# ESP32_LHCbit.net
KiCad netlist of a schematic drawn in Altium Designer
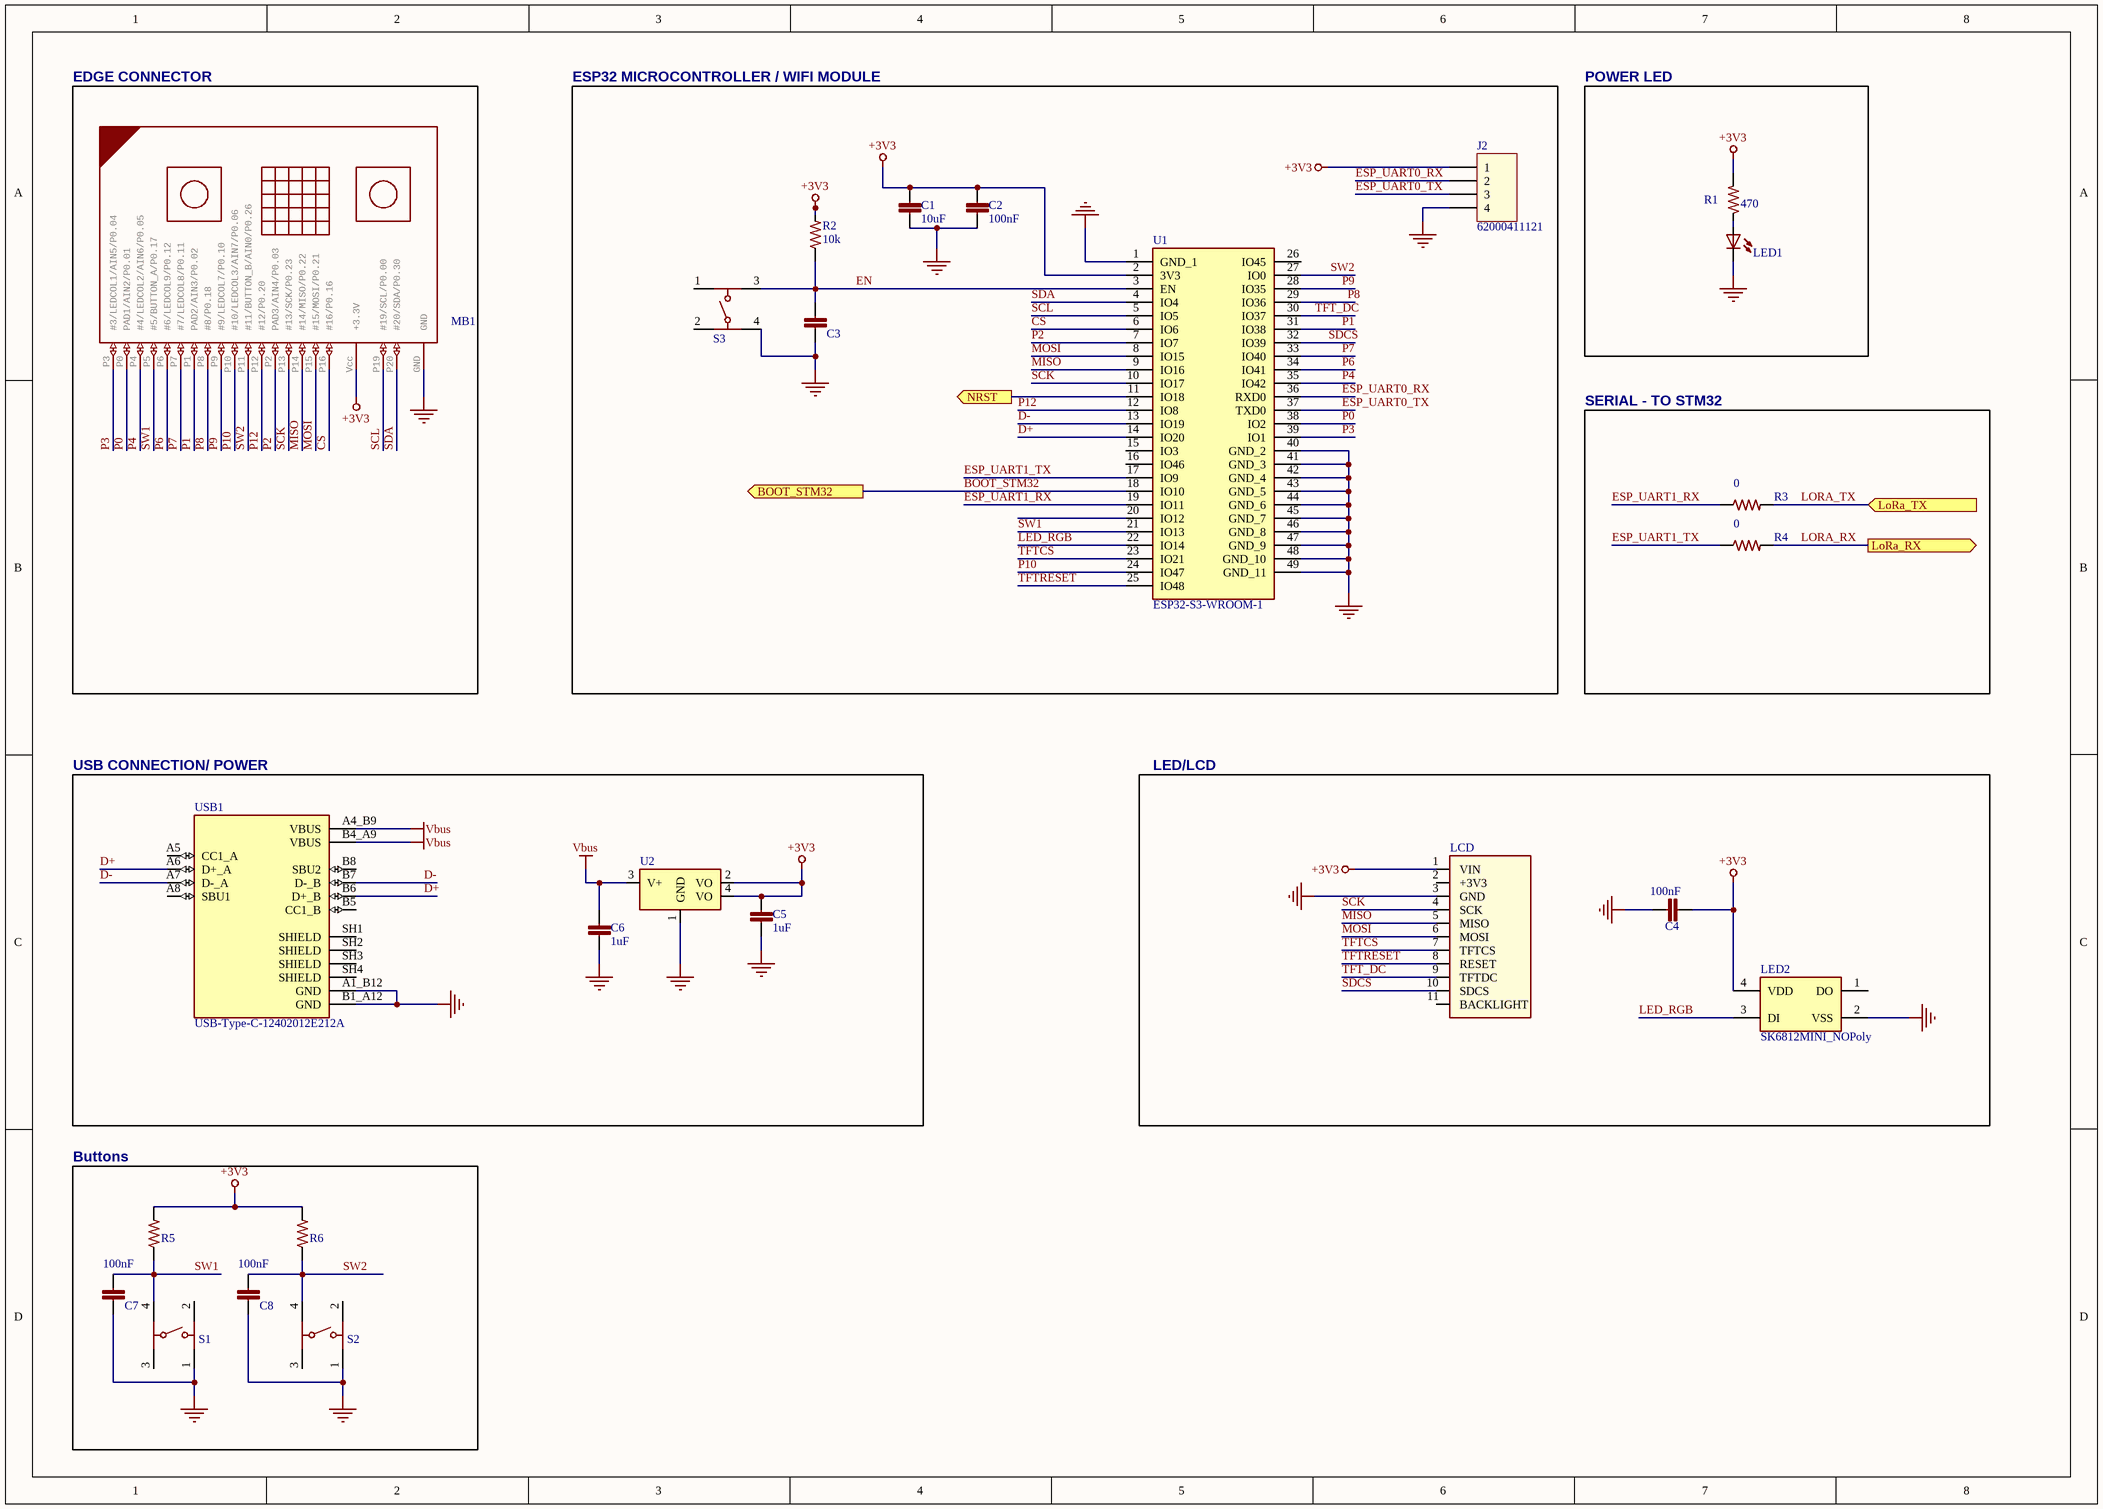
[diagram p0: ESP32_LHCbit.SchDoc]

(export (version "E")
  (design (tool "Eeschema 10.0.6"))
  (components
    (comp (ref "C1")
      (value "10uF")
      (footprint "C0603")
      (fields (field (name "PART NUMBER") "CL10A106KP8NNNC") (field (name "Comment") "C-EUC0603"))
      (libsource (lib "rcl") (part "C-EUC0603"))
    )
    (comp (ref "C2")
      (value "100nF")
      (footprint "C0603")
      (fields (field (name "PART NUMBER") "CC0603KRX7R9BB104") (field (name "Comment") "C-EUC0603"))
      (libsource (lib "rcl") (part "C-EUC0603"))
    )
    (comp (ref "C3")
      (value "C-EUC0402")
      (footprint "C0402")
      (fields (field (name "PART NUMBER") "C0402C104K8"))
      (libsource (lib "") (part "C-EUC0402_1"))
    )
    (comp (ref "C4")
      (value "100nF")
      (footprint "C0402")
      (fields (field (name "PART NUMBER") "C0402C104K8") (field (name "Comment") "C-EUC0402"))
      (libsource (lib "rcl") (part "C-EUC0402"))
    )
    (comp (ref "C5")
      (value "1uF")
      (footprint "C0603")
      (fields (field (name "PART NUMBER") "CL10A105KO8NNNC") (field (name "Comment") "C-EUC0603"))
      (libsource (lib "") (part "C-EUC0603_1"))
    )
    (comp (ref "C6")
      (value "1uF")
      (footprint "C0603")
      (fields (field (name "PART NUMBER") "CL10A105KO8NNNC") (field (name "Comment") "C-EUC0603"))
      (libsource (lib "") (part "C-EUC0603_1"))
    )
    (comp (ref "C7")
      (value "100nF")
      (footprint "C0402")
      (fields (field (name "PART NUMBER") "C0402C104K8") (field (name "Comment") "C-EUC0402"))
      (libsource (lib "") (part "C-EUC0402_1"))
    )
    (comp (ref "C8")
      (value "100nF")
      (footprint "C0402")
      (fields (field (name "PART NUMBER") "C0402C104K8") (field (name "Comment") "C-EUC0402"))
      (libsource (lib "") (part "C-EUC0402_1"))
    )
    (comp (ref "J2")
      (value "62000411121")
      (footprint "62000411121")
      (description "WR-PHD 2.00 mm THT Pin Header, 4p")
      (libsource (lib "Male_header_200mm") (part "62000411121"))
    )
    (comp (ref "LCD")
      (value "Adafruit 0.96\"  TFT LCD")
      (footprint "ADafruit 0.96 Display")
      (libsource (lib "TE") (part "Adafruit 0.96{dblquote}  TFT LCD"))
    )
    (comp (ref "LED1")
      (value "~")
      (footprint "CHIPLED_0805")
      (fields (field (name "PART NUMBER") "AP2012EC"))
      (libsource (lib "led") (part "LEDCHIPLED_0805"))
    )
    (comp (ref "LED2")
      (value "SK6812MINI_NOPoly")
      (footprint "WS2812BMINI_no_poly")
      (description "SMD RGB (WS2812/SK6812MINI) 3535")
      (fields (field (name "PART NUMBER") "SK6812MINI"))
      (libsource (lib "led") (part "SK6812MINI_NOPoly"))
    )
    (comp (ref "MB1")
      (value "MICRO:BIT_EDGE")
      (footprint "MICROBIT_EDGE")
      (libsource (lib "TE") (part "MICRO{colon}BIT_EDGE"))
    )
    (comp (ref "R1")
      (value "470")
      (footprint "R0603")
      (fields (field (name "PART NUMBER") "RC0603FR-07470RL") (field (name "Comment") "R-US_R0603"))
      (libsource (lib "rcl") (part "R-US_R0603"))
    )
    (comp (ref "R2")
      (value "10k")
      (footprint "R0402")
      (fields (field (name "PART NUMBER") "RC0402FR-0710KL") (field (name "Comment") "R-US_R0402"))
      (libsource (lib "rcl") (part "R-US_R0402"))
    )
    (comp (ref "R3")
      (value "0")
      (footprint "R0402")
      (fields (field (name "PART NUMBER") "PA0402-R-070RL") (field (name "Comment") "R-US_R0402"))
      (libsource (lib "rcl") (part "R-US_R0402"))
    )
    (comp (ref "R4")
      (value "0")
      (footprint "R0402")
      (fields (field (name "PART NUMBER") "PA0402-R-070RL") (field (name "Comment") "R-US_R0402"))
      (libsource (lib "rcl") (part "R-US_R0402"))
    )
    (comp (ref "R5")
      (value "R-US_R0402")
      (footprint "R0402")
      (fields (field (name "PART NUMBER") "RC0402FR-0710KL"))
      (libsource (lib "rcl") (part "R-US_R0402"))
    )
    (comp (ref "R6")
      (value "R-US_R0402")
      (footprint "R0402")
      (fields (field (name "PART NUMBER") "RC0402FR-0710KL"))
      (libsource (lib "rcl") (part "R-US_R0402"))
    )
    (comp (ref "S1")
      (value "DTSM-6")
      (footprint "4301x20438x6_6x6x4.3_DTSM-6")
      (description "WS-TASV 6x6mm Tact Switch, SMD version")
      (libsource (lib "Switches") (part "DTSM-6"))
    )
    (comp (ref "S2")
      (value "DTSM-6")
      (footprint "4301x20438x6_6x6x4.3_DTSM-6")
      (description "WS-TASV 6x6mm Tact Switch, SMD version")
      (libsource (lib "Switches") (part "DTSM-6"))
    )
    (comp (ref "S3")
      (value "434153017835")
      (footprint "434153017835_3.2x2.9x1.7")
      (description "WS-TASV 3.5x2.9mm Tact Switch, J-Bend SMD version")
      (libsource (lib "Switches") (part "434153017835"))
    )
    (comp (ref "U1")
      (value "ESP32-S3-WROOM-1")
      (footprint "ESP32S3WROOM1N16R2")
      (description "Integrated Circuit")
      (fields (field (name "PART NUMBER") "ESP32-S3-WROOM-1-N16R2"))
      (libsource (lib "TE") (part "ESP32-S3-WROOM-1"))
    )
    (comp (ref "U2")
      (value "NCP1117LP")
      (footprint "SOT223")
      (fields (field (name "PART NUMBER") "TLV1117LV33DCYR"))
      (libsource (lib "TE") (part "NCP1117LP"))
    )
    (comp (ref "USB1")
      (value "USB-Type-C-12402012E212A")
      (footprint "AMPHENOL_12402012E212A")
      (description "USB2.0, Type C")
      (fields (field (name "PART NUMBER") "TYPEC-304-ACP16"))
      (libsource (lib "TE") (part "USB-Type-C-12402012E212A"))
    )
  )
  (nets
    (net (code "1") (name "+3V3") (class "Default")
      (node (ref "C1") (pin "1") (pinfunction "1_1") (pintype "passive"))
      (node (ref "C2") (pin "1") (pinfunction "1_1") (pintype "passive"))
      (node (ref "C4") (pin "2") (pinfunction "2_2") (pintype "passive"))
      (node (ref "C5") (pin "1") (pinfunction "1_1") (pintype "passive"))
      (node (ref "J2") (pin "1") (pinfunction "1_1") (pintype "passive"))
      (node (ref "LCD") (pin "1") (pinfunction "VIN_1") (pintype "power_in"))
      (node (ref "LED2") (pin "4") (pinfunction "VDD_4") (pintype "passive"))
      (node (ref "MB1") (pin "Vcc") (pinfunction "+3.3V_Vcc") (pintype "power_in"))
      (node (ref "R1") (pin "2") (pinfunction "2_2") (pintype "passive"))
      (node (ref "R2") (pin "2") (pinfunction "2_2") (pintype "passive"))
      (node (ref "R5") (pin "2") (pinfunction "2_2") (pintype "passive"))
      (node (ref "R6") (pin "2") (pinfunction "2_2") (pintype "passive"))
      (node (ref "U1") (pin "2") (pinfunction "3V3_2") (pintype "passive"))
      (node (ref "U2") (pin "2") (pinfunction "VO_2") (pintype "passive"))
      (node (ref "U2") (pin "4") (pinfunction "VO_4") (pintype "passive"))
    )
    (net (code "2") (name "/BOOT_STM32") (class "Default")
      (node (ref "U1") (pin "18") (pinfunction "IO10_18") (pintype "passive"))
    )
    (net (code "3") (name "/CS") (class "Default")
      (node (ref "MB1") (pin "P16") (pinfunction "#16/P0.16_P16") (pintype "bidirectional"))
      (node (ref "U1") (pin "6") (pinfunction "IO6_6") (pintype "passive"))
    )
    (net (code "4") (name "/D+") (class "Default")
      (node (ref "U1") (pin "14") (pinfunction "IO20_14") (pintype "passive"))
      (node (ref "USB1") (pin "A6") (pinfunction "D+_A_A6") (pintype "bidirectional"))
      (node (ref "USB1") (pin "B6") (pinfunction "D+_B_B6") (pintype "bidirectional"))
    )
    (net (code "5") (name "/D-") (class "Default")
      (node (ref "U1") (pin "13") (pinfunction "IO19_13") (pintype "passive"))
      (node (ref "USB1") (pin "A7") (pinfunction "D-_A_A7") (pintype "bidirectional"))
      (node (ref "USB1") (pin "B7") (pinfunction "D-_B_B7") (pintype "bidirectional"))
    )
    (net (code "6") (name "/EN") (class "Default")
      (node (ref "C3") (pin "1") (pinfunction "1_1") (pintype "passive"))
      (node (ref "R2") (pin "1") (pinfunction "1_1") (pintype "passive"))
      (node (ref "S3") (pin "3") (pinfunction "3_3") (pintype "passive"))
      (node (ref "U1") (pin "3") (pinfunction "EN_3") (pintype "passive"))
    )
    (net (code "7") (name "/ESP_UART0_RX") (class "Default")
      (node (ref "J2") (pin "2") (pinfunction "2_2") (pintype "passive"))
      (node (ref "U1") (pin "36") (pinfunction "RXD0_36") (pintype "passive"))
    )
    (net (code "8") (name "/ESP_UART0_TX") (class "Default")
      (node (ref "J2") (pin "3") (pinfunction "3_3") (pintype "passive"))
      (node (ref "U1") (pin "37") (pinfunction "TXD0_37") (pintype "passive"))
    )
    (net (code "9") (name "/ESP_UART1_RX") (class "Default")
      (node (ref "R3") (pin "1") (pinfunction "1_1") (pintype "passive"))
      (node (ref "U1") (pin "19") (pinfunction "IO11_19") (pintype "passive"))
    )
    (net (code "10") (name "/ESP_UART1_TX") (class "Default")
      (node (ref "R4") (pin "1") (pinfunction "1_1") (pintype "passive"))
      (node (ref "U1") (pin "17") (pinfunction "IO9_17") (pintype "passive"))
    )
    (net (code "11") (name "/LED_RGB") (class "Default")
      (node (ref "LED2") (pin "3") (pinfunction "DI_3") (pintype "passive"))
      (node (ref "U1") (pin "22") (pinfunction "IO14_22") (pintype "passive"))
    )
    (net (code "12") (name "/LORA_RX") (class "Default")
      (node (ref "R4") (pin "2") (pinfunction "2_2") (pintype "passive"))
    )
    (net (code "13") (name "/LORA_TX") (class "Default")
      (node (ref "R3") (pin "2") (pinfunction "2_2") (pintype "passive"))
    )
    (net (code "14") (name "/MISO") (class "Default")
      (node (ref "LCD") (pin "5") (pinfunction "MISO_5") (pintype "passive"))
      (node (ref "MB1") (pin "P14") (pinfunction "#14/MISO/P0.22_P14") (pintype "bidirectional"))
      (node (ref "U1") (pin "9") (pinfunction "IO16_9") (pintype "passive"))
    )
    (net (code "15") (name "/MOSI") (class "Default")
      (node (ref "LCD") (pin "6") (pinfunction "MOSI_6") (pintype "passive"))
      (node (ref "MB1") (pin "P15") (pinfunction "#15/MOSI/P0.21_P15") (pintype "bidirectional"))
      (node (ref "U1") (pin "8") (pinfunction "IO15_8") (pintype "passive"))
    )
    (net (code "16") (name "/NRST") (class "Default")
      (node (ref "U1") (pin "11") (pinfunction "IO18_11") (pintype "passive"))
    )
    (net (code "17") (name "/P0") (class "Default")
      (node (ref "MB1") (pin "P0") (pinfunction "PAD1/AIN2/P0.01_P0") (pintype "bidirectional"))
      (node (ref "U1") (pin "38") (pinfunction "IO2_38") (pintype "passive"))
    )
    (net (code "18") (name "/P1") (class "Default")
      (node (ref "MB1") (pin "P1") (pinfunction "PAD2/AIN3/P0.02_P1") (pintype "bidirectional"))
      (node (ref "U1") (pin "31") (pinfunction "IO38_31") (pintype "passive"))
    )
    (net (code "19") (name "/P2") (class "Default")
      (node (ref "MB1") (pin "P2") (pinfunction "PAD3/AIN4/P0.03_P2") (pintype "bidirectional"))
      (node (ref "U1") (pin "7") (pinfunction "IO7_7") (pintype "passive"))
    )
    (net (code "20") (name "/P3") (class "Default")
      (node (ref "MB1") (pin "P3") (pinfunction "#3/LEDCOL1/AIN5/P0.04_P3") (pintype "bidirectional"))
      (node (ref "U1") (pin "39") (pinfunction "IO1_39") (pintype "passive"))
    )
    (net (code "21") (name "/P4") (class "Default")
      (node (ref "MB1") (pin "P4") (pinfunction "#4/LEDCOL2/AIN6/P0.05_P4") (pintype "bidirectional"))
      (node (ref "U1") (pin "35") (pinfunction "IO42_35") (pintype "passive"))
    )
    (net (code "22") (name "/P6") (class "Default")
      (node (ref "MB1") (pin "P6") (pinfunction "#6/LEDCOL9/P0.12_P6") (pintype "bidirectional"))
      (node (ref "U1") (pin "34") (pinfunction "IO41_34") (pintype "passive"))
    )
    (net (code "23") (name "/P7") (class "Default")
      (node (ref "MB1") (pin "P7") (pinfunction "#7/LEDCOL8/P0.11_P7") (pintype "bidirectional"))
      (node (ref "U1") (pin "33") (pinfunction "IO40_33") (pintype "passive"))
    )
    (net (code "24") (name "/P8") (class "Default")
      (node (ref "MB1") (pin "P8") (pinfunction "#8/P0.18_P8") (pintype "bidirectional"))
      (node (ref "U1") (pin "29") (pinfunction "IO36_29") (pintype "passive"))
    )
    (net (code "25") (name "/P9") (class "Default")
      (node (ref "MB1") (pin "P9") (pinfunction "#9/LEDCOL7/P0.10_P9") (pintype "bidirectional"))
      (node (ref "U1") (pin "28") (pinfunction "IO35_28") (pintype "passive"))
    )
    (net (code "26") (name "/P10") (class "Default")
      (node (ref "MB1") (pin "P10") (pinfunction "#10/LEDCOL3/AIN7/P0.06_P10") (pintype "bidirectional"))
      (node (ref "U1") (pin "24") (pinfunction "IO47_24") (pintype "passive"))
    )
    (net (code "27") (name "/P12") (class "Default")
      (node (ref "MB1") (pin "P12") (pinfunction "#12/P0.20_P12") (pintype "bidirectional"))
      (node (ref "U1") (pin "12") (pinfunction "IO8_12") (pintype "passive"))
    )
    (net (code "28") (name "/SCK") (class "Default")
      (node (ref "LCD") (pin "4") (pinfunction "SCK_4") (pintype "passive"))
      (node (ref "MB1") (pin "P13") (pinfunction "#13/SCK/P0.23_P13") (pintype "bidirectional"))
      (node (ref "U1") (pin "10") (pinfunction "IO17_10") (pintype "passive"))
    )
    (net (code "29") (name "/SCL") (class "Default")
      (node (ref "MB1") (pin "P19") (pinfunction "#19/SCL/P0.00_P19") (pintype "bidirectional"))
      (node (ref "U1") (pin "5") (pinfunction "IO5_5") (pintype "passive"))
    )
    (net (code "30") (name "/SDA") (class "Default")
      (node (ref "MB1") (pin "P20") (pinfunction "#20/SDA/P0.30_P20") (pintype "bidirectional"))
      (node (ref "U1") (pin "4") (pinfunction "IO4_4") (pintype "passive"))
    )
    (net (code "31") (name "/SDCS") (class "Default")
      (node (ref "LCD") (pin "10") (pinfunction "SDCS_10") (pintype "passive"))
      (node (ref "U1") (pin "32") (pinfunction "IO39_32") (pintype "passive"))
    )
    (net (code "32") (name "/SW1") (class "Default")
      (node (ref "C7") (pin "1") (pinfunction "1_1") (pintype "passive"))
      (node (ref "MB1") (pin "P5") (pinfunction "#5/BUTTON_A/P0.17_P5") (pintype "bidirectional"))
      (node (ref "R5") (pin "1") (pinfunction "1_1") (pintype "passive"))
      (node (ref "S1") (pin "4") (pinfunction "4_4") (pintype "passive"))
      (node (ref "U1") (pin "21") (pinfunction "IO13_21") (pintype "passive"))
    )
    (net (code "33") (name "/SW2") (class "Default")
      (node (ref "C8") (pin "1") (pinfunction "1_1") (pintype "passive"))
      (node (ref "MB1") (pin "P11") (pinfunction "#11/BUTTON_B/AIN0/P0.26_P11") (pintype "bidirectional"))
      (node (ref "R6") (pin "1") (pinfunction "1_1") (pintype "passive"))
      (node (ref "S2") (pin "4") (pinfunction "4_4") (pintype "passive"))
      (node (ref "U1") (pin "27") (pinfunction "IO0_27") (pintype "passive"))
    )
    (net (code "34") (name "/TFTCS") (class "Default")
      (node (ref "LCD") (pin "7") (pinfunction "TFTCS_7") (pintype "passive"))
      (node (ref "U1") (pin "23") (pinfunction "IO21_23") (pintype "passive"))
    )
    (net (code "35") (name "/TFTRESET") (class "Default")
      (node (ref "LCD") (pin "8") (pinfunction "RESET_8") (pintype "passive"))
      (node (ref "U1") (pin "25") (pinfunction "IO48_25") (pintype "passive"))
    )
    (net (code "36") (name "/TFT_DC") (class "Default")
      (node (ref "LCD") (pin "9") (pinfunction "TFTDC_9") (pintype "passive"))
      (node (ref "U1") (pin "30") (pinfunction "IO37_30") (pintype "passive"))
    )
    (net (code "37") (name "GND") (class "Default")
      (node (ref "C1") (pin "2") (pinfunction "2_2") (pintype "passive"))
      (node (ref "C2") (pin "2") (pinfunction "2_2") (pintype "passive"))
      (node (ref "C3") (pin "2") (pinfunction "2_2") (pintype "passive"))
      (node (ref "C4") (pin "1") (pinfunction "1_1") (pintype "passive"))
      (node (ref "C5") (pin "2") (pinfunction "2_2") (pintype "passive"))
      (node (ref "C6") (pin "2") (pinfunction "2_2") (pintype "passive"))
      (node (ref "C7") (pin "2") (pinfunction "2_2") (pintype "passive"))
      (node (ref "C8") (pin "2") (pinfunction "2_2") (pintype "passive"))
      (node (ref "J2") (pin "4") (pinfunction "4_4") (pintype "passive"))
      (node (ref "LCD") (pin "3") (pinfunction "GND_3") (pintype "passive"))
      (node (ref "LED1") (pin "C") (pinfunction "C_C") (pintype "passive"))
      (node (ref "LED2") (pin "2") (pinfunction "VSS_2") (pintype "passive"))
      (node (ref "MB1") (pin "GND") (pinfunction "GND_GND") (pintype "power_in"))
      (node (ref "S1") (pin "1") (pinfunction "1_1") (pintype "passive"))
      (node (ref "S2") (pin "1") (pinfunction "1_1") (pintype "passive"))
      (node (ref "S3") (pin "4") (pinfunction "4_4") (pintype "passive"))
      (node (ref "U1") (pin "1") (pinfunction "GND_1_1") (pintype "passive"))
      (node (ref "U1") (pin "40") (pinfunction "GND_2_40") (pintype "passive"))
      (node (ref "U1") (pin "41") (pinfunction "GND_3_41") (pintype "passive"))
      (node (ref "U1") (pin "42") (pinfunction "GND_4_42") (pintype "passive"))
      (node (ref "U1") (pin "43") (pinfunction "GND_5_43") (pintype "passive"))
      (node (ref "U1") (pin "44") (pinfunction "GND_6_44") (pintype "passive"))
      (node (ref "U1") (pin "45") (pinfunction "GND_7_45") (pintype "passive"))
      (node (ref "U1") (pin "46") (pinfunction "GND_8_46") (pintype "passive"))
      (node (ref "U1") (pin "47") (pinfunction "GND_9_47") (pintype "passive"))
      (node (ref "U1") (pin "48") (pinfunction "GND_10_48") (pintype "passive"))
      (node (ref "U1") (pin "49") (pinfunction "GND_11_49") (pintype "passive"))
      (node (ref "U2") (pin "1") (pinfunction "GND_1") (pintype "power_in"))
      (node (ref "USB1") (pin "A1_B12") (pinfunction "GND_A1_B12") (pintype "power_in"))
      (node (ref "USB1") (pin "B1_A12") (pinfunction "GND_B1_A12") (pintype "power_in"))
    )
    (net (code "38") (name "Net-(LED1-PadA)") (class "Default")
      (node (ref "LED1") (pin "A") (pinfunction "A_A") (pintype "passive"))
      (node (ref "R1") (pin "1") (pinfunction "1_1") (pintype "passive"))
    )
    (net (code "39") (name "Vbus") (class "Default")
      (node (ref "C6") (pin "1") (pinfunction "1_1") (pintype "passive"))
      (node (ref "U2") (pin "3") (pinfunction "V+_3") (pintype "power_in"))
      (node (ref "USB1") (pin "A4_B9") (pinfunction "VBUS_A4_B9") (pintype "power_in"))
      (node (ref "USB1") (pin "B4_A9") (pinfunction "VBUS_B4_A9") (pintype "power_in"))
    )
    (net (code "40") (name "unconnected-(LCD-+3V3-Pad2)") (class "Default")
      (node (ref "LCD") (pin "2") (pinfunction "+3V3_2") (pintype "power_in"))
    )
    (net (code "41") (name "unconnected-(LCD-BACKLIGHT-Pad11)") (class "Default")
      (node (ref "LCD") (pin "11") (pinfunction "BACKLIGHT_11") (pintype "passive"))
    )
    (net (code "42") (name "unconnected-(LED2-DO-Pad1)") (class "Default")
      (node (ref "LED2") (pin "1") (pinfunction "DO_1") (pintype "passive"))
    )
    (net (code "43") (name "unconnected-(S1-Pad2)") (class "Default")
      (node (ref "S1") (pin "2") (pinfunction "2_2") (pintype "passive"))
    )
    (net (code "44") (name "unconnected-(S1-Pad3)") (class "Default")
      (node (ref "S1") (pin "3") (pinfunction "3_3") (pintype "passive"))
    )
    (net (code "45") (name "unconnected-(S2-Pad2)") (class "Default")
      (node (ref "S2") (pin "2") (pinfunction "2_2") (pintype "passive"))
    )
    (net (code "46") (name "unconnected-(S2-Pad3)") (class "Default")
      (node (ref "S2") (pin "3") (pinfunction "3_3") (pintype "passive"))
    )
    (net (code "47") (name "unconnected-(S3-Pad1)") (class "Default")
      (node (ref "S3") (pin "1") (pinfunction "1_1") (pintype "passive"))
    )
    (net (code "48") (name "unconnected-(S3-Pad2)") (class "Default")
      (node (ref "S3") (pin "2") (pinfunction "2_2") (pintype "passive"))
    )
    (net (code "49") (name "unconnected-(U1-IO3-Pad15)") (class "Default")
      (node (ref "U1") (pin "15") (pinfunction "IO3_15") (pintype "passive"))
    )
    (net (code "50") (name "unconnected-(U1-IO12-Pad20)") (class "Default")
      (node (ref "U1") (pin "20") (pinfunction "IO12_20") (pintype "passive"))
    )
    (net (code "51") (name "unconnected-(U1-IO45-Pad26)") (class "Default")
      (node (ref "U1") (pin "26") (pinfunction "IO45_26") (pintype "passive"))
    )
    (net (code "52") (name "unconnected-(U1-IO46-Pad16)") (class "Default")
      (node (ref "U1") (pin "16") (pinfunction "IO46_16") (pintype "passive"))
    )
    (net (code "53") (name "unconnected-(USB1-CC1_A-PadA5)") (class "Default")
      (node (ref "USB1") (pin "A5") (pinfunction "CC1_A_A5") (pintype "bidirectional"))
    )
    (net (code "54") (name "unconnected-(USB1-CC1_B-PadB5)") (class "Default")
      (node (ref "USB1") (pin "B5") (pinfunction "CC1_B_B5") (pintype "bidirectional"))
    )
    (net (code "55") (name "unconnected-(USB1-SBU1-PadA8)") (class "Default")
      (node (ref "USB1") (pin "A8") (pinfunction "SBU1_A8") (pintype "bidirectional"))
    )
    (net (code "56") (name "unconnected-(USB1-SBU2-PadB8)") (class "Default")
      (node (ref "USB1") (pin "B8") (pinfunction "SBU2_B8") (pintype "bidirectional"))
    )
    (net (code "57") (name "unconnected-(USB1-SHIELD-PadSH1)") (class "Default")
      (node (ref "USB1") (pin "SH1") (pinfunction "SHIELD_SH1") (pintype "passive"))
    )
    (net (code "58") (name "unconnected-(USB1-SHIELD-PadSH2)") (class "Default")
      (node (ref "USB1") (pin "SH2") (pinfunction "SHIELD_SH2") (pintype "passive"))
    )
    (net (code "59") (name "unconnected-(USB1-SHIELD-PadSH3)") (class "Default")
      (node (ref "USB1") (pin "SH3") (pinfunction "SHIELD_SH3") (pintype "passive"))
    )
    (net (code "60") (name "unconnected-(USB1-SHIELD-PadSH4)") (class "Default")
      (node (ref "USB1") (pin "SH4") (pinfunction "SHIELD_SH4") (pintype "passive"))
    )
  )
)
